# digital.net
KiCad netlist of a schematic drawn in EAGLE
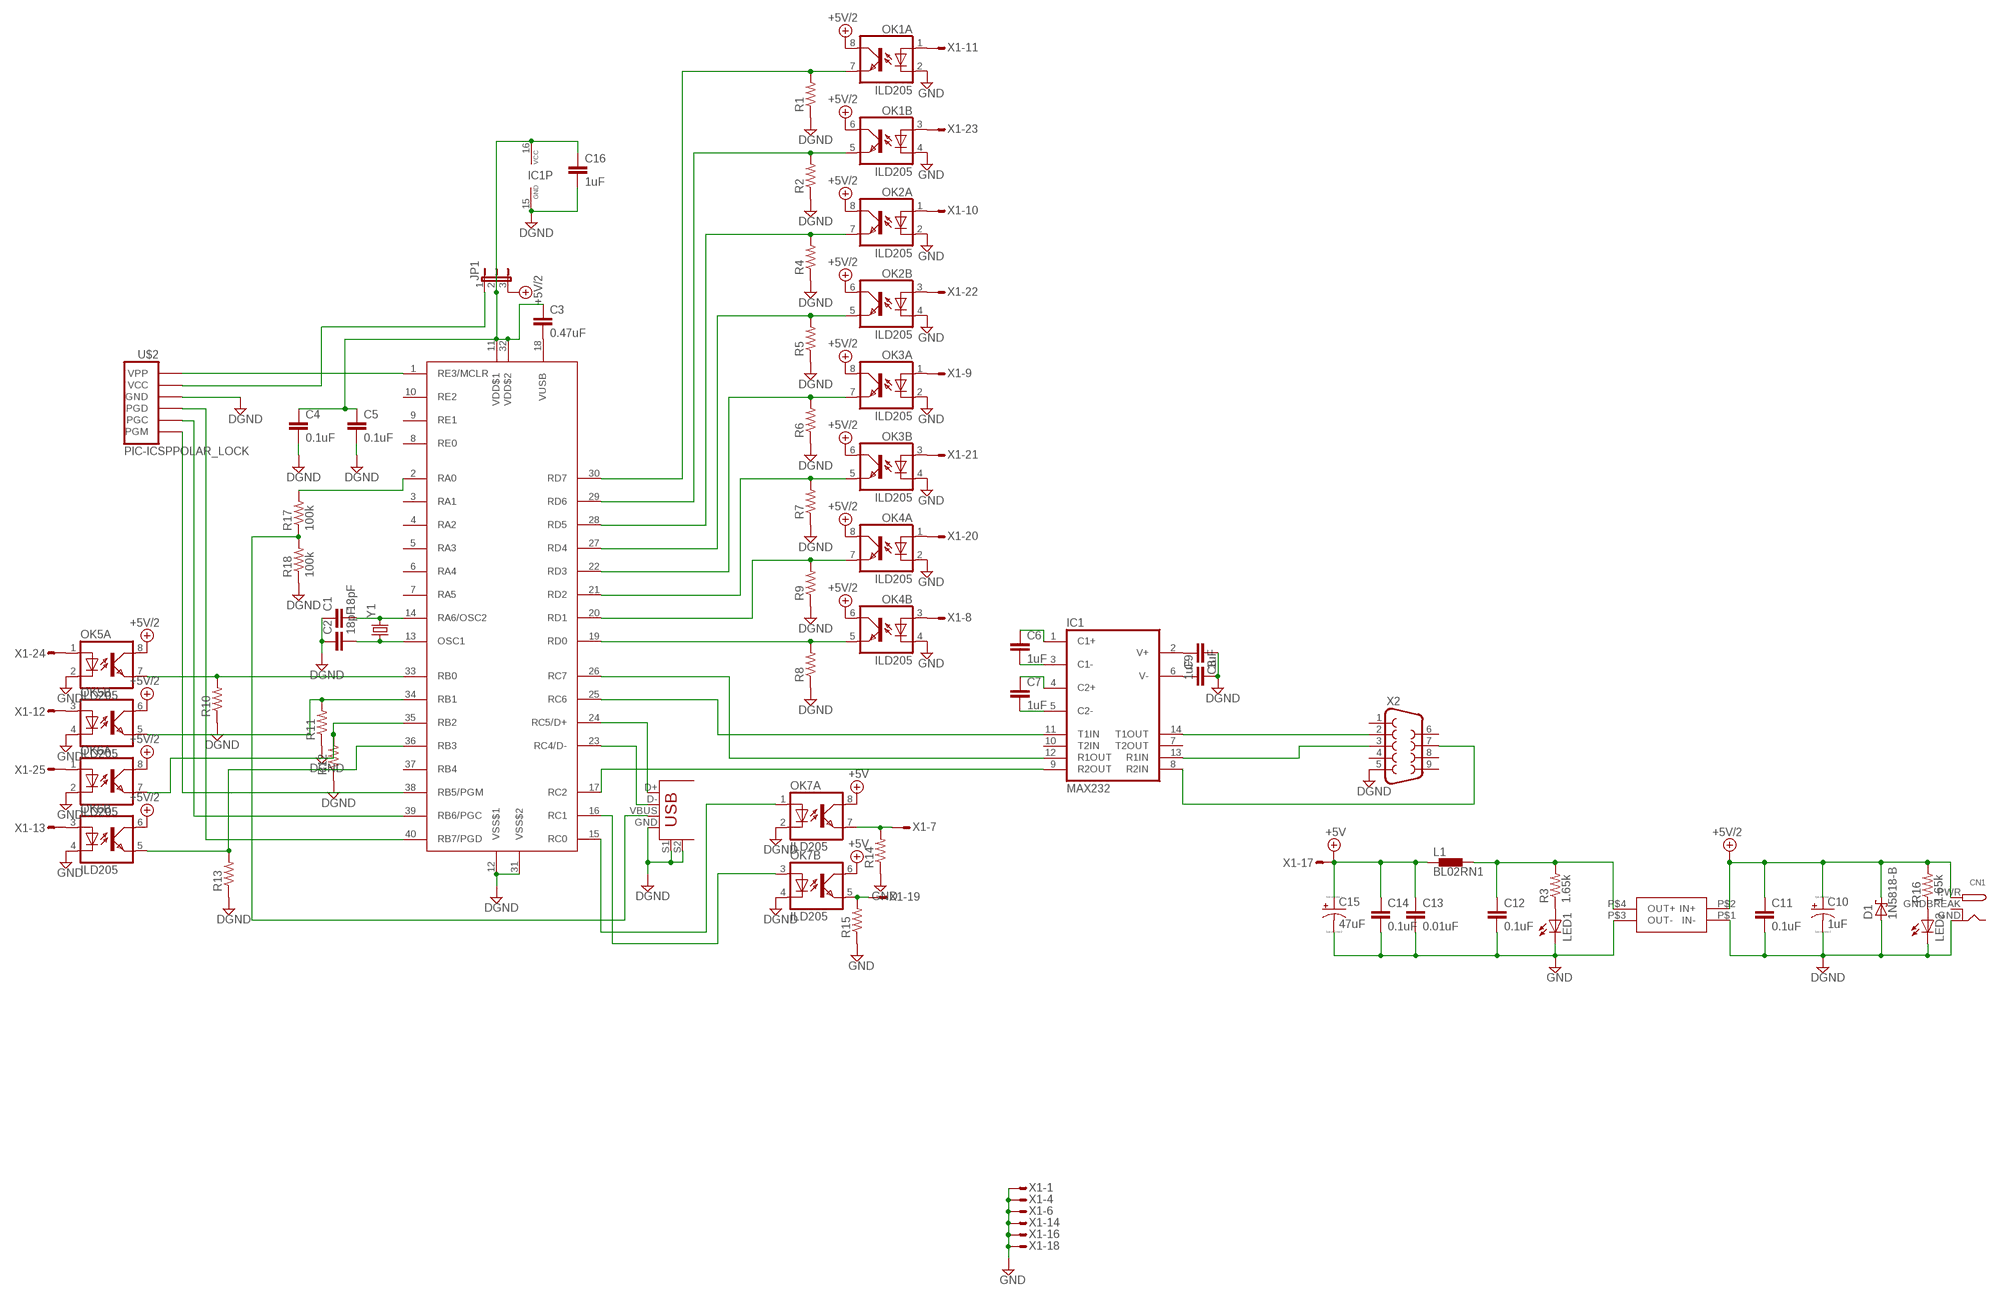
[diagram p0: schematic, sheet 1]

(export (version "E")
  (design (tool "Eeschema 10.0.6"))
  (components
    (comp (ref "C1")
      (value "18pF")
      (footprint "eagle-import:C050-025X075")
      (libsource (lib "eagle-import") (part "C-EU050-025X075"))
    )
    (comp (ref "C2")
      (value "18pF")
      (footprint "eagle-import:C050-025X075")
      (libsource (lib "eagle-import") (part "C-EU050-025X075"))
    )
    (comp (ref "C3")
      (value "0.47uF")
      (footprint "eagle-import:C050-025X075")
      (libsource (lib "eagle-import") (part "C-EU050-025X075"))
    )
    (comp (ref "C4")
      (value "0.1uF")
      (footprint "eagle-import:C050-025X075")
      (libsource (lib "eagle-import") (part "C-EU050-025X075"))
    )
    (comp (ref "C5")
      (value "0.1uF")
      (footprint "eagle-import:C050-025X075")
      (libsource (lib "eagle-import") (part "C-EU050-025X075"))
    )
    (comp (ref "C6")
      (value "1uF")
      (footprint "eagle-import:C050-025X075")
      (libsource (lib "eagle-import") (part "C-EU050-025X075"))
    )
    (comp (ref "C7")
      (value "1uF")
      (footprint "eagle-import:C050-025X075")
      (libsource (lib "eagle-import") (part "C-EU050-025X075"))
    )
    (comp (ref "C8")
      (value "1uF")
      (footprint "eagle-import:C050-025X075")
      (libsource (lib "eagle-import") (part "C-EU050-025X075"))
    )
    (comp (ref "C9")
      (value "1uF")
      (footprint "eagle-import:C050-025X075")
      (libsource (lib "eagle-import") (part "C-EU050-025X075"))
    )
    (comp (ref "C10")
      (value "1uF")
      (footprint "eagle-import:E5-8,5")
      (libsource (lib "eagle-import") (part "CPOL-USE5-8.5"))
    )
    (comp (ref "C11")
      (value "0.1uF")
      (footprint "eagle-import:C050-025X075")
      (libsource (lib "eagle-import") (part "C-EU050-025X075"))
    )
    (comp (ref "C12")
      (value "0.1uF")
      (footprint "eagle-import:C050-025X075")
      (libsource (lib "eagle-import") (part "C-EU050-025X075"))
    )
    (comp (ref "C13")
      (value "0.01uF")
      (footprint "eagle-import:C050-025X075")
      (libsource (lib "eagle-import") (part "C-EU050-025X075"))
    )
    (comp (ref "C14")
      (value "0.1uF")
      (footprint "eagle-import:C050-025X075")
      (libsource (lib "eagle-import") (part "C-EU050-025X075"))
    )
    (comp (ref "C15")
      (value "47uF")
      (footprint "eagle-import:E5-8,5")
      (libsource (lib "eagle-import") (part "CPOL-USE5-8.5"))
    )
    (comp (ref "C16")
      (value "1uF")
      (footprint "eagle-import:C050-025X075")
      (libsource (lib "eagle-import") (part "C-EU050-025X075"))
    )
    (comp (ref "CN1")
      (value "DCBARRELPTH")
      (footprint "eagle-import:DCJACK_2MM_PTH")
      (libsource (lib "eagle-import") (part "DCBARRELPTH"))
    )
    (comp (ref "D1")
      (value "1N5818-B")
      (footprint "eagle-import:DO41-7.6")
      (libsource (lib "eagle-import") (part "1N5818-B"))
    )
    (comp (ref "IC1")
      (value "MAX232")
      (footprint "eagle-import:DIL16")
      (fields (field (name "MF") "MAXIM") (field (name "MPN") "MAX232ACPE+"))
      (libsource (lib "eagle-import") (part "MAX232"))
    )
    (comp (ref "J1")
      (value "USB+SHIELD")
      (footprint "eagle-import:USB-B-PTH")
      (libsource (lib "eagle-import") (part "USB+SHIELD"))
    )
    (comp (ref "JP1")
      (value "JP2E")
      (footprint "eagle-import:JP2")
      (libsource (lib "eagle-import") (part "JP2E"))
    )
    (comp (ref "L1")
      (value "BL02RN1")
      (footprint "eagle-import:BL02RN1")
      (libsource (lib "eagle-import") (part "BL02RN1"))
    )
    (comp (ref "LED1")
      (value "LED3MM")
      (footprint "eagle-import:LED3MM")
      (libsource (lib "eagle-import") (part "LED3MM"))
    )
    (comp (ref "LED2")
      (value "LED3MM")
      (footprint "eagle-import:LED3MM")
      (libsource (lib "eagle-import") (part "LED3MM"))
    )
    (comp (ref "OK1")
      (value "ILD205")
      (footprint "eagle-import:SOIC08")
      (fields (field (name "MF") "VISHAY/TELEFUNKEN") (field (name "MPN") "ILD205T"))
      (libsource (lib "eagle-import") (part "ILD205"))
    )
    (comp (ref "OK2")
      (value "ILD205")
      (footprint "eagle-import:SOIC08")
      (fields (field (name "MF") "VISHAY/TELEFUNKEN") (field (name "MPN") "ILD205T"))
      (libsource (lib "eagle-import") (part "ILD205"))
    )
    (comp (ref "OK3")
      (value "ILD205")
      (footprint "eagle-import:SOIC08")
      (fields (field (name "MF") "VISHAY/TELEFUNKEN") (field (name "MPN") "ILD205T"))
      (libsource (lib "eagle-import") (part "ILD205"))
    )
    (comp (ref "OK4")
      (value "ILD205")
      (footprint "eagle-import:SOIC08")
      (fields (field (name "MF") "VISHAY/TELEFUNKEN") (field (name "MPN") "ILD205T"))
      (libsource (lib "eagle-import") (part "ILD205"))
    )
    (comp (ref "OK5")
      (value "ILD205")
      (footprint "eagle-import:SOIC08")
      (fields (field (name "MF") "VISHAY/TELEFUNKEN") (field (name "MPN") "ILD205T"))
      (libsource (lib "eagle-import") (part "ILD205"))
    )
    (comp (ref "OK6")
      (value "ILD205")
      (footprint "eagle-import:SOIC08")
      (fields (field (name "MF") "VISHAY/TELEFUNKEN") (field (name "MPN") "ILD205T"))
      (libsource (lib "eagle-import") (part "ILD205"))
    )
    (comp (ref "OK7")
      (value "ILD205")
      (footprint "eagle-import:SOIC08")
      (fields (field (name "MF") "VISHAY/TELEFUNKEN") (field (name "MPN") "ILD205T"))
      (libsource (lib "eagle-import") (part "ILD205"))
    )
    (comp (ref "R1")
      (value "R-US_0204/2V")
      (footprint "eagle-import:0204V")
      (libsource (lib "eagle-import") (part "R-US_0204/2V"))
    )
    (comp (ref "R2")
      (value "R-US_0204/2V")
      (footprint "eagle-import:0204V")
      (libsource (lib "eagle-import") (part "R-US_0204/2V"))
    )
    (comp (ref "R3")
      (value "1.65k")
      (footprint "eagle-import:0204V")
      (libsource (lib "eagle-import") (part "R-US_0204/2V"))
    )
    (comp (ref "R4")
      (value "R-US_0204/2V")
      (footprint "eagle-import:0204V")
      (libsource (lib "eagle-import") (part "R-US_0204/2V"))
    )
    (comp (ref "R5")
      (value "R-US_0204/2V")
      (footprint "eagle-import:0204V")
      (libsource (lib "eagle-import") (part "R-US_0204/2V"))
    )
    (comp (ref "R6")
      (value "R-US_0204/2V")
      (footprint "eagle-import:0204V")
      (libsource (lib "eagle-import") (part "R-US_0204/2V"))
    )
    (comp (ref "R7")
      (value "R-US_0204/2V")
      (footprint "eagle-import:0204V")
      (libsource (lib "eagle-import") (part "R-US_0204/2V"))
    )
    (comp (ref "R8")
      (value "R-US_0204/2V")
      (footprint "eagle-import:0204V")
      (libsource (lib "eagle-import") (part "R-US_0204/2V"))
    )
    (comp (ref "R9")
      (value "R-US_0204/2V")
      (footprint "eagle-import:0204V")
      (libsource (lib "eagle-import") (part "R-US_0204/2V"))
    )
    (comp (ref "R10")
      (value "R-US_0204/2V")
      (footprint "eagle-import:0204V")
      (libsource (lib "eagle-import") (part "R-US_0204/2V"))
    )
    (comp (ref "R11")
      (value "R-US_0204/2V")
      (footprint "eagle-import:0204V")
      (libsource (lib "eagle-import") (part "R-US_0204/2V"))
    )
    (comp (ref "R12")
      (value "R-US_0204/2V")
      (footprint "eagle-import:0204V")
      (libsource (lib "eagle-import") (part "R-US_0204/2V"))
    )
    (comp (ref "R13")
      (value "R-US_0204/2V")
      (footprint "eagle-import:0204V")
      (libsource (lib "eagle-import") (part "R-US_0204/2V"))
    )
    (comp (ref "R14")
      (value "R-US_0204/2V")
      (footprint "eagle-import:0204V")
      (libsource (lib "eagle-import") (part "R-US_0204/2V"))
    )
    (comp (ref "R15")
      (value "R-US_0204/2V")
      (footprint "eagle-import:0204V")
      (libsource (lib "eagle-import") (part "R-US_0204/2V"))
    )
    (comp (ref "R16")
      (value "1.65k")
      (footprint "eagle-import:0204V")
      (libsource (lib "eagle-import") (part "R-US_0204/2V"))
    )
    (comp (ref "R17")
      (value "100k")
      (footprint "eagle-import:0204V")
      (libsource (lib "eagle-import") (part "R-US_0204/2V"))
    )
    (comp (ref "R18")
      (value "100k")
      (footprint "eagle-import:0204V")
      (libsource (lib "eagle-import") (part "R-US_0204/2V"))
    )
    (comp (ref "U$1")
      (value "PIC18F4458")
      (footprint "eagle-import:DIL40")
      (libsource (lib "eagle-import") (part "PIC18F4458"))
    )
    (comp (ref "U$2")
      (value "PIC-ICSPPOLAR_LOCK")
      (footprint "eagle-import:MOLEX-1X6_LOCK")
      (libsource (lib "eagle-import") (part "PIC-ICSPPOLAR_LOCK"))
    )
    (comp (ref "U$3")
      (value "ROL-0505S")
      (footprint "eagle-import:SIP4")
      (libsource (lib "eagle-import") (part "ROL-0505S"))
    )
    (comp (ref "X1")
      (value "M25HS")
      (footprint "eagle-import:M25H")
      (libsource (lib "eagle-import") (part "M25?SH"))
    )
    (comp (ref "X2")
      (value "F09HP")
      (footprint "eagle-import:F09HP")
      (libsource (lib "eagle-import") (part "F09HP"))
    )
    (comp (ref "Y1")
      (value "CRYSTALHC49US")
      (footprint "eagle-import:HC49US")
      (libsource (lib "eagle-import") (part "CRYSTALHC49US"))
    )
  )
  (nets
    (net (code "1") (name "+5V") (class "Default")
      (node (ref "C13") (pin "1") (pinfunction "1_1") (pintype "passive"))
      (node (ref "C14") (pin "1") (pinfunction "1_1") (pintype "passive"))
      (node (ref "C15") (pin "+") (pinfunction "+_+") (pintype "passive"))
      (node (ref "L1") (pin "1") (pinfunction "1_1") (pintype "passive"))
      (node (ref "OK7") (pin "6") (pinfunction "COL_6") (pintype "passive"))
      (node (ref "OK7") (pin "8") (pinfunction "COL_8") (pintype "passive"))
      (node (ref "X1") (pin "17") (pinfunction "M_17") (pintype "passive"))
    )
    (net (code "2") (name "+5V{slash}2") (class "Default")
      (node (ref "C10") (pin "+") (pinfunction "+_+") (pintype "passive"))
      (node (ref "C11") (pin "1") (pinfunction "1_1") (pintype "passive"))
      (node (ref "CN1") (pin "PWR") (pinfunction "PWR_PWR") (pintype "power_in"))
      (node (ref "D1") (pin "C") (pinfunction "C_C") (pintype "passive"))
      (node (ref "JP1") (pin "3") (pinfunction "3_3") (pintype "passive"))
      (node (ref "OK1") (pin "6") (pinfunction "COL_6") (pintype "passive"))
      (node (ref "OK1") (pin "8") (pinfunction "COL_8") (pintype "passive"))
      (node (ref "OK2") (pin "6") (pinfunction "COL_6") (pintype "passive"))
      (node (ref "OK2") (pin "8") (pinfunction "COL_8") (pintype "passive"))
      (node (ref "OK3") (pin "6") (pinfunction "COL_6") (pintype "passive"))
      (node (ref "OK3") (pin "8") (pinfunction "COL_8") (pintype "passive"))
      (node (ref "OK4") (pin "6") (pinfunction "COL_6") (pintype "passive"))
      (node (ref "OK4") (pin "8") (pinfunction "COL_8") (pintype "passive"))
      (node (ref "OK5") (pin "6") (pinfunction "COL_6") (pintype "passive"))
      (node (ref "OK5") (pin "8") (pinfunction "COL_8") (pintype "passive"))
      (node (ref "OK6") (pin "6") (pinfunction "COL_6") (pintype "passive"))
      (node (ref "OK6") (pin "8") (pinfunction "COL_8") (pintype "passive"))
      (node (ref "R16") (pin "2") (pinfunction "2_2") (pintype "passive"))
      (node (ref "U$3") (pin "P$2") (pinfunction "IN+_P$2") (pintype "power_in"))
    )
    (net (code "3") (name "/GNDBREAK") (class "Default")
      (node (ref "CN1") (pin "GNDBREAK") (pinfunction "GNDBREAK_GNDBREAK") (pintype "power_in"))
    )
    (net (code "4") (name "DGND") (class "Default")
      (node (ref "C1") (pin "1") (pinfunction "1_1") (pintype "passive"))
      (node (ref "C10") (pin "-") (pinfunction "-_-") (pintype "passive"))
      (node (ref "C11") (pin "2") (pinfunction "2_2") (pintype "passive"))
      (node (ref "C16") (pin "2") (pinfunction "2_2") (pintype "passive"))
      (node (ref "C2") (pin "1") (pinfunction "1_1") (pintype "passive"))
      (node (ref "C4") (pin "2") (pinfunction "2_2") (pintype "passive"))
      (node (ref "C5") (pin "2") (pinfunction "2_2") (pintype "passive"))
      (node (ref "C8") (pin "1") (pinfunction "1_1") (pintype "passive"))
      (node (ref "C9") (pin "2") (pinfunction "2_2") (pintype "passive"))
      (node (ref "CN1") (pin "GND") (pinfunction "GND_GND") (pintype "power_in"))
      (node (ref "D1") (pin "A") (pinfunction "A_A") (pintype "passive"))
      (node (ref "IC1") (pin "15") (pinfunction "GND_15") (pintype "power_in"))
      (node (ref "J1") (pin "GND") (pinfunction "GND_GND") (pintype "bidirectional"))
      (node (ref "J1") (pin "S1") (pinfunction "S1_S1") (pintype "bidirectional"))
      (node (ref "J1") (pin "S2") (pinfunction "S2_S2") (pintype "bidirectional"))
      (node (ref "LED2") (pin "K") (pinfunction "C_K") (pintype "passive"))
      (node (ref "OK7") (pin "2") (pinfunction "C_2") (pintype "passive"))
      (node (ref "OK7") (pin "4") (pinfunction "C_4") (pintype "passive"))
      (node (ref "R1") (pin "1") (pinfunction "1_1") (pintype "passive"))
      (node (ref "R10") (pin "1") (pinfunction "1_1") (pintype "passive"))
      (node (ref "R11") (pin "1") (pinfunction "1_1") (pintype "passive"))
      (node (ref "R12") (pin "1") (pinfunction "1_1") (pintype "passive"))
      (node (ref "R13") (pin "1") (pinfunction "1_1") (pintype "passive"))
      (node (ref "R18") (pin "1") (pinfunction "1_1") (pintype "passive"))
      (node (ref "R2") (pin "1") (pinfunction "1_1") (pintype "passive"))
      (node (ref "R4") (pin "1") (pinfunction "1_1") (pintype "passive"))
      (node (ref "R5") (pin "1") (pinfunction "1_1") (pintype "passive"))
      (node (ref "R6") (pin "1") (pinfunction "1_1") (pintype "passive"))
      (node (ref "R7") (pin "1") (pinfunction "1_1") (pintype "passive"))
      (node (ref "R8") (pin "1") (pinfunction "1_1") (pintype "passive"))
      (node (ref "R9") (pin "1") (pinfunction "1_1") (pintype "passive"))
      (node (ref "U$1") (pin "12") (pinfunction "VSS$1_12") (pintype "bidirectional"))
      (node (ref "U$1") (pin "31") (pinfunction "VSS$2_31") (pintype "bidirectional"))
      (node (ref "U$2") (pin "4") (pinfunction "GND_4") (pintype "bidirectional"))
      (node (ref "U$3") (pin "P$1") (pinfunction "IN-_P$1") (pintype "power_in"))
      (node (ref "X2") (pin "5") (pinfunction "5_5") (pintype "passive"))
    )
    (net (code "5") (name "GND") (class "Default")
      (node (ref "C12") (pin "2") (pinfunction "2_2") (pintype "passive"))
      (node (ref "C13") (pin "2") (pinfunction "2_2") (pintype "passive"))
      (node (ref "C14") (pin "2") (pinfunction "2_2") (pintype "passive"))
      (node (ref "C15") (pin "-") (pinfunction "-_-") (pintype "passive"))
      (node (ref "LED1") (pin "K") (pinfunction "C_K") (pintype "passive"))
      (node (ref "OK1") (pin "2") (pinfunction "C_2") (pintype "passive"))
      (node (ref "OK1") (pin "4") (pinfunction "C_4") (pintype "passive"))
      (node (ref "OK2") (pin "2") (pinfunction "C_2") (pintype "passive"))
      (node (ref "OK2") (pin "4") (pinfunction "C_4") (pintype "passive"))
      (node (ref "OK3") (pin "2") (pinfunction "C_2") (pintype "passive"))
      (node (ref "OK3") (pin "4") (pinfunction "C_4") (pintype "passive"))
      (node (ref "OK4") (pin "2") (pinfunction "C_2") (pintype "passive"))
      (node (ref "OK4") (pin "4") (pinfunction "C_4") (pintype "passive"))
      (node (ref "OK5") (pin "2") (pinfunction "C_2") (pintype "passive"))
      (node (ref "OK5") (pin "4") (pinfunction "C_4") (pintype "passive"))
      (node (ref "OK6") (pin "2") (pinfunction "C_2") (pintype "passive"))
      (node (ref "OK6") (pin "4") (pinfunction "C_4") (pintype "passive"))
      (node (ref "R14") (pin "1") (pinfunction "1_1") (pintype "passive"))
      (node (ref "R15") (pin "1") (pinfunction "1_1") (pintype "passive"))
      (node (ref "U$3") (pin "P$3") (pinfunction "OUT-_P$3") (pintype "power_in"))
      (node (ref "X1") (pin "1") (pinfunction "M_1") (pintype "passive"))
      (node (ref "X1") (pin "14") (pinfunction "M_14") (pintype "passive"))
      (node (ref "X1") (pin "16") (pinfunction "M_16") (pintype "passive"))
      (node (ref "X1") (pin "18") (pinfunction "M_18") (pintype "passive"))
      (node (ref "X1") (pin "4") (pinfunction "M_4") (pintype "passive"))
      (node (ref "X1") (pin "6") (pinfunction "M_6") (pintype "passive"))
    )
    (net (code "6") (name "Net-(IC1A-C1+)") (class "Default")
      (node (ref "C6") (pin "1") (pinfunction "1_1") (pintype "passive"))
      (node (ref "IC1") (pin "1") (pinfunction "C1+_1") (pintype "bidirectional"))
    )
    (net (code "7") (name "Net-(IC1A-C1-)") (class "Default")
      (node (ref "C6") (pin "2") (pinfunction "2_2") (pintype "passive"))
      (node (ref "IC1") (pin "3") (pinfunction "C1-_3") (pintype "bidirectional"))
    )
    (net (code "8") (name "Net-(IC1A-C2+)") (class "Default")
      (node (ref "C7") (pin "1") (pinfunction "1_1") (pintype "passive"))
      (node (ref "IC1") (pin "4") (pinfunction "C2+_4") (pintype "bidirectional"))
    )
    (net (code "9") (name "Net-(IC1A-C2-)") (class "Default")
      (node (ref "C7") (pin "2") (pinfunction "2_2") (pintype "passive"))
      (node (ref "IC1") (pin "5") (pinfunction "C2-_5") (pintype "bidirectional"))
    )
    (net (code "10") (name "Net-(IC1A-R1IN)") (class "Default")
      (node (ref "IC1") (pin "13") (pinfunction "R1IN_13") (pintype "input"))
      (node (ref "X2") (pin "3") (pinfunction "3_3") (pintype "passive"))
    )
    (net (code "11") (name "Net-(IC1A-R1OUT)") (class "Default")
      (node (ref "IC1") (pin "12") (pinfunction "R1OUT_12") (pintype "output"))
      (node (ref "U$1") (pin "26") (pinfunction "RC7_26") (pintype "bidirectional"))
    )
    (net (code "12") (name "Net-(IC1A-R2IN)") (class "Default")
      (node (ref "IC1") (pin "8") (pinfunction "R2IN_8") (pintype "input"))
      (node (ref "X2") (pin "7") (pinfunction "7_7") (pintype "passive"))
    )
    (net (code "13") (name "Net-(IC1A-R2OUT)") (class "Default")
      (node (ref "IC1") (pin "9") (pinfunction "R2OUT_9") (pintype "output"))
      (node (ref "U$1") (pin "17") (pinfunction "RC2_17") (pintype "bidirectional"))
    )
    (net (code "14") (name "Net-(IC1A-T1IN)") (class "Default")
      (node (ref "IC1") (pin "11") (pinfunction "T1IN_11") (pintype "input"))
      (node (ref "U$1") (pin "25") (pinfunction "RC6_25") (pintype "bidirectional"))
    )
    (net (code "15") (name "Net-(IC1A-T1OUT)") (class "Default")
      (node (ref "IC1") (pin "14") (pinfunction "T1OUT_14") (pintype "output"))
      (node (ref "X2") (pin "2") (pinfunction "2_2") (pintype "passive"))
    )
    (net (code "16") (name "Net-(IC1A-V+)") (class "Default")
      (node (ref "C8") (pin "2") (pinfunction "2_2") (pintype "passive"))
      (node (ref "IC1") (pin "2") (pinfunction "V+_2") (pintype "bidirectional"))
    )
    (net (code "17") (name "Net-(IC1A-V-)") (class "Default")
      (node (ref "C9") (pin "1") (pinfunction "1_1") (pintype "passive"))
      (node (ref "IC1") (pin "6") (pinfunction "V-_6") (pintype "bidirectional"))
    )
    (net (code "18") (name "Net-(IC1B-VCC)") (class "Default")
      (node (ref "C16") (pin "1") (pinfunction "1_1") (pintype "passive"))
      (node (ref "C3") (pin "1") (pinfunction "1_1") (pintype "passive"))
      (node (ref "C4") (pin "1") (pinfunction "1_1") (pintype "passive"))
      (node (ref "C5") (pin "1") (pinfunction "1_1") (pintype "passive"))
      (node (ref "IC1") (pin "16") (pinfunction "VCC_16") (pintype "power_in"))
      (node (ref "JP1") (pin "2") (pinfunction "2_2") (pintype "passive"))
      (node (ref "U$1") (pin "11") (pinfunction "VDD$1_11") (pintype "bidirectional"))
      (node (ref "U$1") (pin "32") (pinfunction "VDD$2_32") (pintype "bidirectional"))
    )
    (net (code "19") (name "Net-(J1-PadVBUS)") (class "Default")
      (node (ref "J1") (pin "VBUS") (pinfunction "VBUS_VBUS") (pintype "bidirectional"))
      (node (ref "R17") (pin "1") (pinfunction "1_1") (pintype "passive"))
      (node (ref "R18") (pin "2") (pinfunction "2_2") (pintype "passive"))
    )
    (net (code "20") (name "Net-(LED1-PadA)") (class "Default")
      (node (ref "LED1") (pin "A") (pinfunction "A_A") (pintype "passive"))
      (node (ref "R3") (pin "1") (pinfunction "1_1") (pintype "passive"))
    )
    (net (code "21") (name "Net-(LED2-PadA)") (class "Default")
      (node (ref "LED2") (pin "A") (pinfunction "A_A") (pintype "passive"))
      (node (ref "R16") (pin "1") (pinfunction "1_1") (pintype "passive"))
    )
    (net (code "22") (name "Net-(OK1A-A)") (class "Default")
      (node (ref "OK1") (pin "1") (pinfunction "A_1") (pintype "passive"))
      (node (ref "X1") (pin "11") (pinfunction "M_11") (pintype "passive"))
    )
    (net (code "23") (name "Net-(OK1A-EMIT)") (class "Default")
      (node (ref "OK1") (pin "7") (pinfunction "EMIT_7") (pintype "passive"))
      (node (ref "R1") (pin "2") (pinfunction "2_2") (pintype "passive"))
      (node (ref "U$1") (pin "30") (pinfunction "RD7_30") (pintype "bidirectional"))
    )
    (net (code "24") (name "Net-(OK1B-A)") (class "Default")
      (node (ref "OK1") (pin "3") (pinfunction "A_3") (pintype "passive"))
      (node (ref "X1") (pin "23") (pinfunction "M_23") (pintype "passive"))
    )
    (net (code "25") (name "Net-(OK1B-EMIT)") (class "Default")
      (node (ref "OK1") (pin "5") (pinfunction "EMIT_5") (pintype "passive"))
      (node (ref "R2") (pin "2") (pinfunction "2_2") (pintype "passive"))
      (node (ref "U$1") (pin "29") (pinfunction "RD6_29") (pintype "bidirectional"))
    )
    (net (code "26") (name "Net-(OK2A-A)") (class "Default")
      (node (ref "OK2") (pin "1") (pinfunction "A_1") (pintype "passive"))
      (node (ref "X1") (pin "10") (pinfunction "M_10") (pintype "passive"))
    )
    (net (code "27") (name "Net-(OK2A-EMIT)") (class "Default")
      (node (ref "OK2") (pin "7") (pinfunction "EMIT_7") (pintype "passive"))
      (node (ref "R4") (pin "2") (pinfunction "2_2") (pintype "passive"))
      (node (ref "U$1") (pin "28") (pinfunction "RD5_28") (pintype "bidirectional"))
    )
    (net (code "28") (name "Net-(OK2B-A)") (class "Default")
      (node (ref "OK2") (pin "3") (pinfunction "A_3") (pintype "passive"))
      (node (ref "X1") (pin "22") (pinfunction "M_22") (pintype "passive"))
    )
    (net (code "29") (name "Net-(OK2B-EMIT)") (class "Default")
      (node (ref "OK2") (pin "5") (pinfunction "EMIT_5") (pintype "passive"))
      (node (ref "R5") (pin "2") (pinfunction "2_2") (pintype "passive"))
      (node (ref "U$1") (pin "27") (pinfunction "RD4_27") (pintype "bidirectional"))
    )
    (net (code "30") (name "Net-(OK3A-A)") (class "Default")
      (node (ref "OK3") (pin "1") (pinfunction "A_1") (pintype "passive"))
      (node (ref "X1") (pin "9") (pinfunction "M_9") (pintype "passive"))
    )
    (net (code "31") (name "Net-(OK3A-EMIT)") (class "Default")
      (node (ref "OK3") (pin "7") (pinfunction "EMIT_7") (pintype "passive"))
      (node (ref "R6") (pin "2") (pinfunction "2_2") (pintype "passive"))
      (node (ref "U$1") (pin "22") (pinfunction "RD3_22") (pintype "bidirectional"))
    )
    (net (code "32") (name "Net-(OK3B-A)") (class "Default")
      (node (ref "OK3") (pin "3") (pinfunction "A_3") (pintype "passive"))
      (node (ref "X1") (pin "21") (pinfunction "M_21") (pintype "passive"))
    )
    (net (code "33") (name "Net-(OK3B-EMIT)") (class "Default")
      (node (ref "OK3") (pin "5") (pinfunction "EMIT_5") (pintype "passive"))
      (node (ref "R7") (pin "2") (pinfunction "2_2") (pintype "passive"))
      (node (ref "U$1") (pin "21") (pinfunction "RD2_21") (pintype "bidirectional"))
    )
    (net (code "34") (name "Net-(OK4A-A)") (class "Default")
      (node (ref "OK4") (pin "1") (pinfunction "A_1") (pintype "passive"))
      (node (ref "X1") (pin "20") (pinfunction "M_20") (pintype "passive"))
    )
    (net (code "35") (name "Net-(OK4A-EMIT)") (class "Default")
      (node (ref "OK4") (pin "7") (pinfunction "EMIT_7") (pintype "passive"))
      (node (ref "R9") (pin "2") (pinfunction "2_2") (pintype "passive"))
      (node (ref "U$1") (pin "20") (pinfunction "RD1_20") (pintype "bidirectional"))
    )
    (net (code "36") (name "Net-(OK4B-A)") (class "Default")
      (node (ref "OK4") (pin "3") (pinfunction "A_3") (pintype "passive"))
      (node (ref "X1") (pin "8") (pinfunction "M_8") (pintype "passive"))
    )
    (net (code "37") (name "Net-(OK4B-EMIT)") (class "Default")
      (node (ref "OK4") (pin "5") (pinfunction "EMIT_5") (pintype "passive"))
      (node (ref "R8") (pin "2") (pinfunction "2_2") (pintype "passive"))
      (node (ref "U$1") (pin "19") (pinfunction "RD0_19") (pintype "bidirectional"))
    )
    (net (code "38") (name "Net-(OK5A-A)") (class "Default")
      (node (ref "OK5") (pin "1") (pinfunction "A_1") (pintype "passive"))
      (node (ref "X1") (pin "24") (pinfunction "M_24") (pintype "passive"))
    )
    (net (code "39") (name "Net-(OK5A-EMIT)") (class "Default")
      (node (ref "OK5") (pin "7") (pinfunction "EMIT_7") (pintype "passive"))
      (node (ref "R10") (pin "2") (pinfunction "2_2") (pintype "passive"))
      (node (ref "U$1") (pin "33") (pinfunction "RB0_33") (pintype "bidirectional"))
    )
    (net (code "40") (name "Net-(OK5B-A)") (class "Default")
      (node (ref "OK5") (pin "3") (pinfunction "A_3") (pintype "passive"))
      (node (ref "X1") (pin "12") (pinfunction "M_12") (pintype "passive"))
    )
    (net (code "41") (name "Net-(OK5B-EMIT)") (class "Default")
      (node (ref "OK5") (pin "5") (pinfunction "EMIT_5") (pintype "passive"))
      (node (ref "R11") (pin "2") (pinfunction "2_2") (pintype "passive"))
      (node (ref "U$1") (pin "34") (pinfunction "RB1_34") (pintype "bidirectional"))
    )
    (net (code "42") (name "Net-(OK6A-A)") (class "Default")
      (node (ref "OK6") (pin "1") (pinfunction "A_1") (pintype "passive"))
      (node (ref "X1") (pin "25") (pinfunction "M_25") (pintype "passive"))
    )
    (net (code "43") (name "Net-(OK6A-EMIT)") (class "Default")
      (node (ref "OK6") (pin "7") (pinfunction "EMIT_7") (pintype "passive"))
      (node (ref "R12") (pin "2") (pinfunction "2_2") (pintype "passive"))
      (node (ref "U$1") (pin "35") (pinfunction "RB2_35") (pintype "bidirectional"))
    )
    (net (code "44") (name "Net-(OK6B-A)") (class "Default")
      (node (ref "OK6") (pin "3") (pinfunction "A_3") (pintype "passive"))
      (node (ref "X1") (pin "13") (pinfunction "M_13") (pintype "passive"))
    )
    (net (code "45") (name "Net-(OK6B-EMIT)") (class "Default")
      (node (ref "OK6") (pin "5") (pinfunction "EMIT_5") (pintype "passive"))
      (node (ref "R13") (pin "2") (pinfunction "2_2") (pintype "passive"))
      (node (ref "U$1") (pin "36") (pinfunction "RB3_36") (pintype "bidirectional"))
    )
    (net (code "46") (name "Net-(OK7A-A)") (class "Default")
      (node (ref "OK7") (pin "1") (pinfunction "A_1") (pintype "passive"))
      (node (ref "U$1") (pin "15") (pinfunction "RC0_15") (pintype "bidirectional"))
    )
    (net (code "47") (name "Net-(OK7A-EMIT)") (class "Default")
      (node (ref "OK7") (pin "7") (pinfunction "EMIT_7") (pintype "passive"))
      (node (ref "R14") (pin "2") (pinfunction "2_2") (pintype "passive"))
      (node (ref "X1") (pin "7") (pinfunction "M_7") (pintype "passive"))
    )
    (net (code "48") (name "Net-(OK7B-A)") (class "Default")
      (node (ref "OK7") (pin "3") (pinfunction "A_3") (pintype "passive"))
      (node (ref "U$1") (pin "16") (pinfunction "RC1_16") (pintype "bidirectional"))
    )
    (net (code "49") (name "Net-(OK7B-EMIT)") (class "Default")
      (node (ref "OK7") (pin "5") (pinfunction "EMIT_5") (pintype "passive"))
      (node (ref "R15") (pin "2") (pinfunction "2_2") (pintype "passive"))
      (node (ref "X1") (pin "19") (pinfunction "M_19") (pintype "passive"))
    )
    (net (code "50") (name "Net-(U$1-OSC1)") (class "Default")
      (node (ref "C2") (pin "2") (pinfunction "2_2") (pintype "passive"))
      (node (ref "U$1") (pin "13") (pinfunction "OSC1_13") (pintype "bidirectional"))
      (node (ref "Y1") (pin "1") (pinfunction "1_1") (pintype "passive"))
    )
    (net (code "51") (name "Net-(U$1-RA0)") (class "Default")
      (node (ref "R17") (pin "2") (pinfunction "2_2") (pintype "passive"))
      (node (ref "U$1") (pin "2") (pinfunction "RA0_2") (pintype "bidirectional"))
    )
    (net (code "52") (name "Net-(U$1-RA6{slash}OSC2)") (class "Default")
      (node (ref "C1") (pin "2") (pinfunction "2_2") (pintype "passive"))
      (node (ref "U$1") (pin "14") (pinfunction "RA6/OSC2_14") (pintype "bidirectional"))
      (node (ref "Y1") (pin "2") (pinfunction "2_2") (pintype "passive"))
    )
    (net (code "53") (name "Net-(U$1-RB5{slash}PGM)") (class "Default")
      (node (ref "U$1") (pin "38") (pinfunction "RB5/PGM_38") (pintype "bidirectional"))
      (node (ref "U$2") (pin "1") (pinfunction "PGM_1") (pintype "bidirectional"))
    )
    (net (code "54") (name "Net-(U$1-RB6{slash}PGC)") (class "Default")
      (node (ref "U$1") (pin "39") (pinfunction "RB6/PGC_39") (pintype "bidirectional"))
      (node (ref "U$2") (pin "2") (pinfunction "PGC_2") (pintype "bidirectional"))
    )
    (net (code "55") (name "Net-(U$1-RB7{slash}PGD)") (class "Default")
      (node (ref "U$1") (pin "40") (pinfunction "RB7/PGD_40") (pintype "bidirectional"))
      (node (ref "U$2") (pin "3") (pinfunction "PGD_3") (pintype "bidirectional"))
    )
    (net (code "56") (name "Net-(U$1-RC4{slash}D-)") (class "Default")
      (node (ref "J1") (pin "D-") (pinfunction "D-_D-") (pintype "bidirectional"))
      (node (ref "U$1") (pin "23") (pinfunction "RC4/D-_23") (pintype "bidirectional"))
    )
    (net (code "57") (name "Net-(U$1-RC5{slash}D+)") (class "Default")
      (node (ref "J1") (pin "D+") (pinfunction "D+_D+") (pintype "bidirectional"))
      (node (ref "U$1") (pin "24") (pinfunction "RC5/D+_24") (pintype "bidirectional"))
    )
    (net (code "58") (name "Net-(U$1-RE3{slash}MCLR)") (class "Default")
      (node (ref "U$1") (pin "1") (pinfunction "RE3/MCLR_1") (pintype "bidirectional"))
      (node (ref "U$2") (pin "6") (pinfunction "VPP_6") (pintype "bidirectional"))
    )
    (net (code "59") (name "Net-(U$1-VUSB)") (class "Default")
      (node (ref "C3") (pin "2") (pinfunction "2_2") (pintype "passive"))
      (node (ref "U$1") (pin "18") (pinfunction "VUSB_18") (pintype "bidirectional"))
    )
    (net (code "60") (name "Net-(U$2-VCC)") (class "Default")
      (node (ref "JP1") (pin "1") (pinfunction "1_1") (pintype "passive"))
      (node (ref "U$2") (pin "5") (pinfunction "VCC_5") (pintype "bidirectional"))
    )
    (net (code "61") (name "Net-(U$3-OUT+)") (class "Default")
      (node (ref "C12") (pin "1") (pinfunction "1_1") (pintype "passive"))
      (node (ref "L1") (pin "2") (pinfunction "2_2") (pintype "passive"))
      (node (ref "R3") (pin "2") (pinfunction "2_2") (pintype "passive"))
      (node (ref "U$3") (pin "P$4") (pinfunction "OUT+_P$4") (pintype "power_in"))
    )
    (net (code "62") (name "unconnected-(IC1A-T2IN-Pad10)") (class "Default")
      (node (ref "IC1") (pin "10") (pinfunction "T2IN_10") (pintype "input"))
    )
    (net (code "63") (name "unconnected-(IC1A-T2OUT-Pad7)") (class "Default")
      (node (ref "IC1") (pin "7") (pinfunction "T2OUT_7") (pintype "output"))
    )
    (net (code "64") (name "unconnected-(U$1-RA1-Pad3)") (class "Default")
      (node (ref "U$1") (pin "3") (pinfunction "RA1_3") (pintype "bidirectional"))
    )
    (net (code "65") (name "unconnected-(U$1-RA2-Pad4)") (class "Default")
      (node (ref "U$1") (pin "4") (pinfunction "RA2_4") (pintype "bidirectional"))
    )
    (net (code "66") (name "unconnected-(U$1-RA3-Pad5)") (class "Default")
      (node (ref "U$1") (pin "5") (pinfunction "RA3_5") (pintype "bidirectional"))
    )
    (net (code "67") (name "unconnected-(U$1-RA4-Pad6)") (class "Default")
      (node (ref "U$1") (pin "6") (pinfunction "RA4_6") (pintype "bidirectional"))
    )
    (net (code "68") (name "unconnected-(U$1-RA5-Pad7)") (class "Default")
      (node (ref "U$1") (pin "7") (pinfunction "RA5_7") (pintype "bidirectional"))
    )
    (net (code "69") (name "unconnected-(U$1-RB4-Pad37)") (class "Default")
      (node (ref "U$1") (pin "37") (pinfunction "RB4_37") (pintype "bidirectional"))
    )
    (net (code "70") (name "unconnected-(U$1-RE0-Pad8)") (class "Default")
      (node (ref "U$1") (pin "8") (pinfunction "RE0_8") (pintype "bidirectional"))
    )
    (net (code "71") (name "unconnected-(U$1-RE1-Pad9)") (class "Default")
      (node (ref "U$1") (pin "9") (pinfunction "RE1_9") (pintype "bidirectional"))
    )
    (net (code "72") (name "unconnected-(U$1-RE2-Pad10)") (class "Default")
      (node (ref "U$1") (pin "10") (pinfunction "RE2_10") (pintype "bidirectional"))
    )
    (net (code "73") (name "unconnected-(X2-Pad1)") (class "Default")
      (node (ref "X2") (pin "1") (pinfunction "1_1") (pintype "passive"))
    )
    (net (code "74") (name "unconnected-(X2-Pad4)") (class "Default")
      (node (ref "X2") (pin "4") (pinfunction "4_4") (pintype "passive"))
    )
    (net (code "75") (name "unconnected-(X2-Pad6)") (class "Default")
      (node (ref "X2") (pin "6") (pinfunction "6_6") (pintype "passive"))
    )
    (net (code "76") (name "unconnected-(X2-Pad8)") (class "Default")
      (node (ref "X2") (pin "8") (pinfunction "8_8") (pintype "passive"))
    )
    (net (code "77") (name "unconnected-(X2-Pad9)") (class "Default")
      (node (ref "X2") (pin "9") (pinfunction "9_9") (pintype "passive"))
    )
  )
)
